# sangaboard_v02.net
KiCad netlist of a schematic drawn in EAGLE
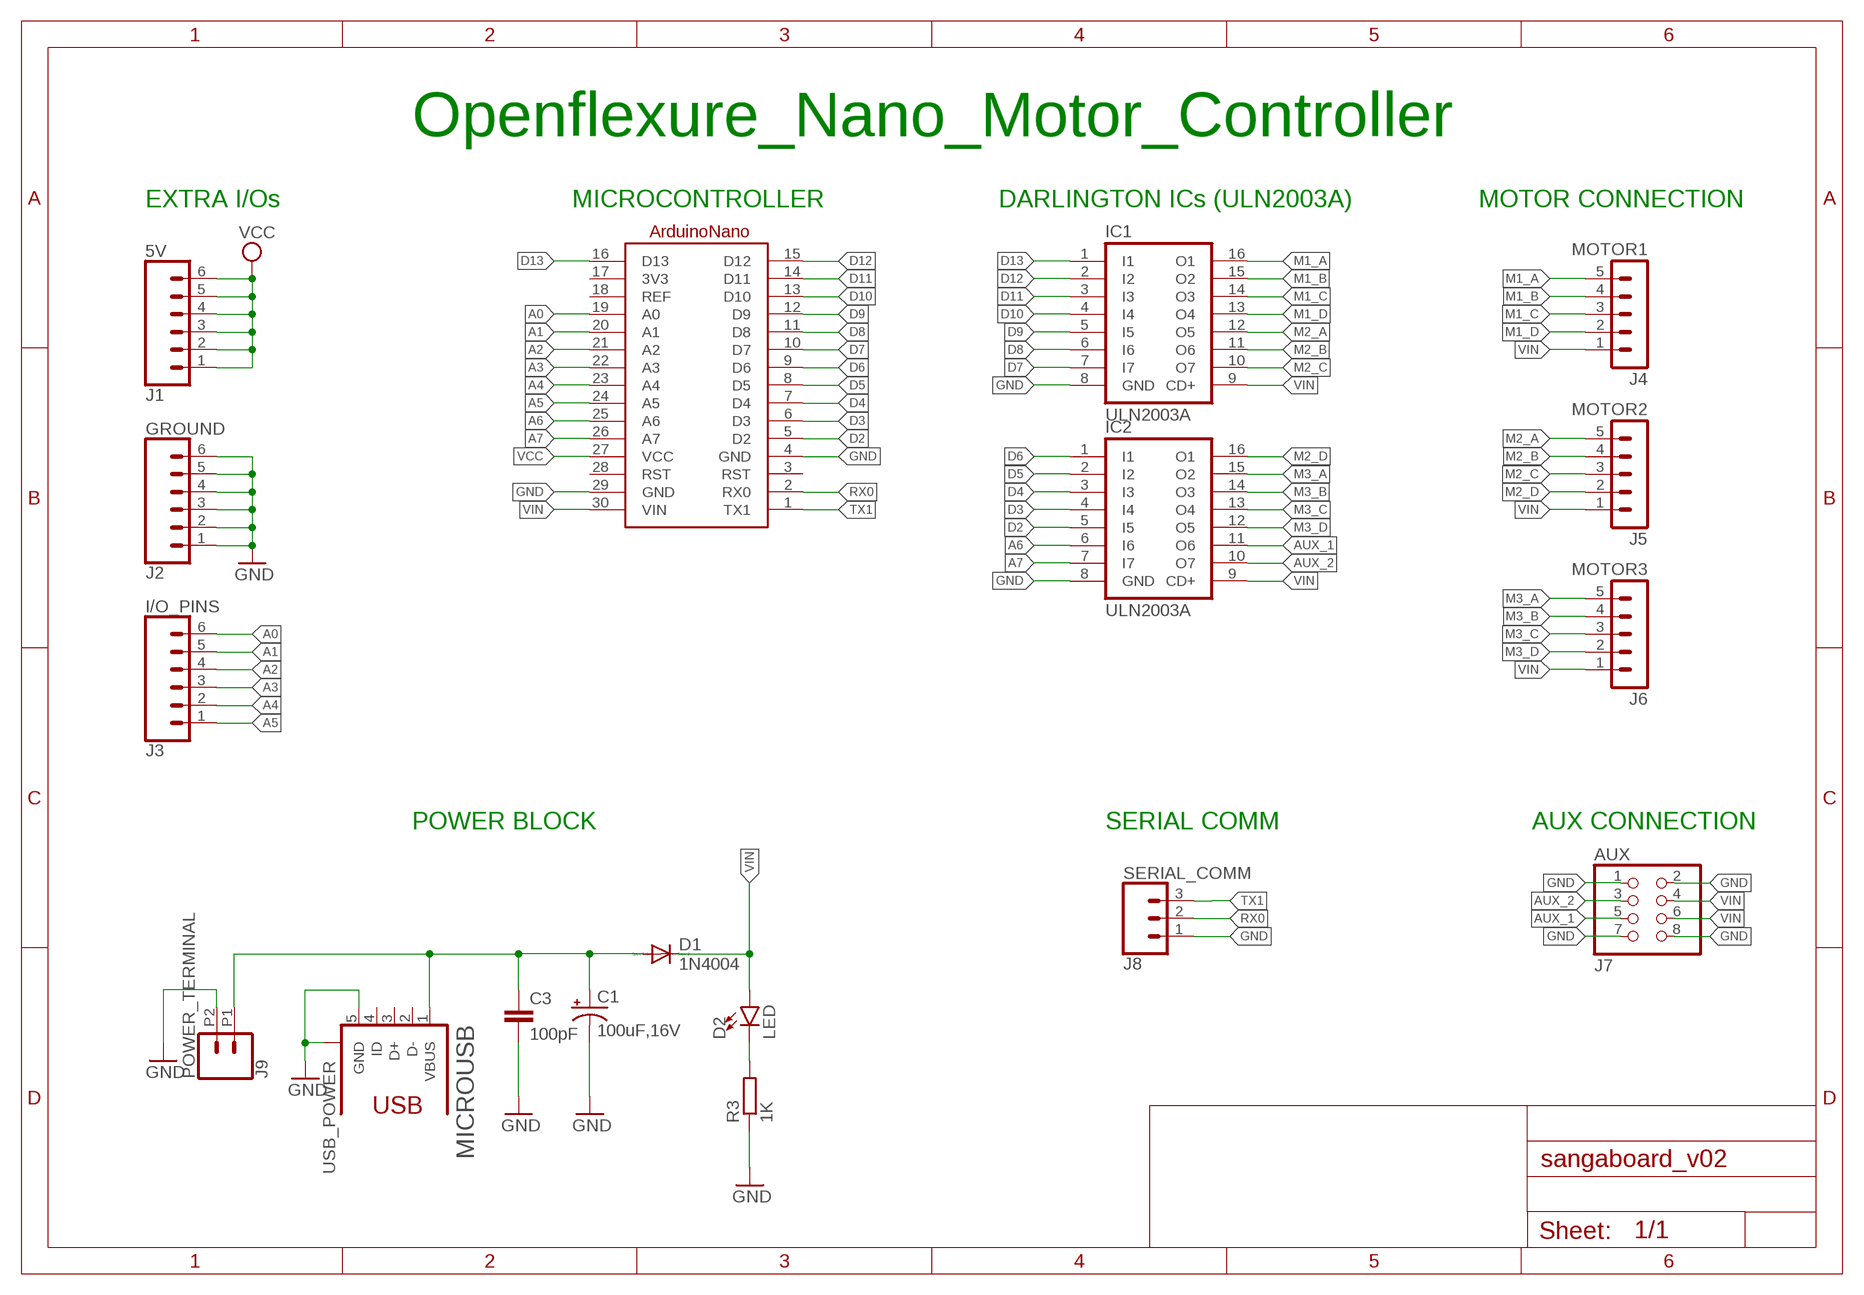
[diagram p0: schematic, sheet 1]

(export (version "E")
  (design (tool "Eeschema 10.0.6"))
  (components
    (comp (ref "5V")
      (value "J1")
      (footprint "eagle-import:1X06_NO_SILK")
      (libsource (lib "eagle-import") (part "CONN_06NO_SILK_NO_POP"))
    )
    (comp (ref "A1")
      (value "Arduino Nano")
      (footprint "eagle-import:ARDUINONANO")
      (libsource (lib "eagle-import") (part "ARDUINONANO"))
    )
    (comp (ref "AUX")
      (value "J7")
      (footprint "eagle-import:2X04")
      (libsource (lib "eagle-import") (part "PINHD-2X4"))
    )
    (comp (ref "C1")
      (value "100uF,16V")
      (footprint "eagle-import:CPOL-RADIAL-2.5MM-6.5MM")
      (libsource (lib "eagle-import") (part "100UF-POLAR-RADIAL-2.5MM-25V-20%"))
    )
    (comp (ref "C3")
      (value "100pF")
      (footprint "eagle-import:CAP-PTH-2.54")
      (libsource (lib "eagle-import") (part "22PF-PTH-2.54MM-200V-5%"))
    )
    (comp (ref "D1")
      (value "1N4004")
      (footprint "eagle-import:DO41-10")
      (libsource (lib "eagle-import") (part "1N4004"))
    )
    (comp (ref "D2")
      (value "LED")
      (footprint "eagle-import:LED_3MM")
      (libsource (lib "eagle-import") (part "LED3MM"))
    )
    (comp (ref "GROUND")
      (value "J2")
      (footprint "eagle-import:1X06_NO_SILK")
      (libsource (lib "eagle-import") (part "CONN_06NO_SILK_NO_POP"))
    )
    (comp (ref "I/O_PINS")
      (value "J3")
      (footprint "eagle-import:1X06_NO_SILK")
      (libsource (lib "eagle-import") (part "CONN_06NO_SILK_NO_POP"))
    )
    (comp (ref "IC1")
      (value "ULN2003A")
      (footprint "eagle-import:DIL16")
      (fields (field (name "MF") "STMicroelectronics"))
      (libsource (lib "eagle-import") (part "ULN2003AN"))
    )
    (comp (ref "IC2")
      (value "ULN2003A")
      (footprint "eagle-import:DIL16")
      (fields (field (name "MF") "STMicroelectronics"))
      (libsource (lib "eagle-import") (part "ULN2003AN"))
    )
    (comp (ref "MICROUSB")
      (value "USB_POWER")
      (footprint "eagle-import:1981584-1")
      (libsource (lib "eagle-import") (part "1981584-1"))
    )
    (comp (ref "MOTOR1")
      (value "J4")
      (footprint "eagle-import:MA05-1")
      (libsource (lib "eagle-import") (part "MA05-1"))
    )
    (comp (ref "MOTOR2")
      (value "J5")
      (footprint "eagle-import:MA05-1")
      (libsource (lib "eagle-import") (part "MA05-1"))
    )
    (comp (ref "MOTOR3")
      (value "J6")
      (footprint "eagle-import:MA05-1")
      (libsource (lib "eagle-import") (part "MA05-1"))
    )
    (comp (ref "POWER_TERMINAL")
      (value "J9")
      (footprint "eagle-import:1X02_2.54_SCREWTERM")
      (libsource (lib "eagle-import") (part "CONN_022.54MM_SCREWTERM"))
    )
    (comp (ref "R3")
      (value "1K")
      (footprint "eagle-import:0207_10")
      (libsource (lib "eagle-import") (part "R-EU_0207/10"))
    )
    (comp (ref "SERIAL_COMM")
      (value "J8")
      (footprint "eagle-import:1X03")
      (libsource (lib "eagle-import") (part "CONN_03"))
    )
  )
  (nets
    (net (code "1") (name "/3V3") (class "Default")
      (node (ref "A1") (pin "17") (pinfunction "3V3_17") (pintype "power_in"))
    )
    (net (code "2") (name "/REF") (class "Default")
      (node (ref "A1") (pin "18") (pinfunction "REF_18") (pintype "power_in"))
    )
    (net (code "3") (name "A0") (class "Default")
      (node (ref "A1") (pin "19") (pinfunction "A0_19") (pintype "input"))
      (node (ref "I/O_PINS") (pin "6") (pinfunction "6_6") (pintype "passive"))
    )
    (net (code "4") (name "A1") (class "Default")
      (node (ref "A1") (pin "20") (pinfunction "A1_20") (pintype "input"))
      (node (ref "I/O_PINS") (pin "5") (pinfunction "5_5") (pintype "passive"))
    )
    (net (code "5") (name "A2") (class "Default")
      (node (ref "A1") (pin "21") (pinfunction "A2_21") (pintype "input"))
      (node (ref "I/O_PINS") (pin "4") (pinfunction "4_4") (pintype "passive"))
    )
    (net (code "6") (name "A3") (class "Default")
      (node (ref "A1") (pin "22") (pinfunction "A3_22") (pintype "input"))
      (node (ref "I/O_PINS") (pin "3") (pinfunction "3_3") (pintype "passive"))
    )
    (net (code "7") (name "A4") (class "Default")
      (node (ref "A1") (pin "23") (pinfunction "A4_23") (pintype "input"))
      (node (ref "I/O_PINS") (pin "2") (pinfunction "2_2") (pintype "passive"))
    )
    (net (code "8") (name "A5") (class "Default")
      (node (ref "A1") (pin "24") (pinfunction "A5_24") (pintype "input"))
      (node (ref "I/O_PINS") (pin "1") (pinfunction "1_1") (pintype "passive"))
    )
    (net (code "9") (name "A6") (class "Default")
      (node (ref "A1") (pin "25") (pinfunction "A6_25") (pintype "input"))
      (node (ref "IC2") (pin "6") (pinfunction "I6_6") (pintype "input"))
    )
    (net (code "10") (name "A7") (class "Default")
      (node (ref "A1") (pin "26") (pinfunction "A7_26") (pintype "input"))
      (node (ref "IC2") (pin "7") (pinfunction "I7_7") (pintype "input"))
    )
    (net (code "11") (name "AUX_1") (class "Default")
      (node (ref "AUX") (pin "5") (pinfunction "5_5") (pintype "passive"))
      (node (ref "IC2") (pin "11") (pinfunction "O6_11") (pintype "open_collector"))
    )
    (net (code "12") (name "AUX_2") (class "Default")
      (node (ref "AUX") (pin "3") (pinfunction "3_3") (pintype "passive"))
      (node (ref "IC2") (pin "10") (pinfunction "O7_10") (pintype "open_collector"))
    )
    (net (code "13") (name "D2") (class "Default")
      (node (ref "A1") (pin "5") (pinfunction "D2_5") (pintype "output"))
      (node (ref "IC2") (pin "5") (pinfunction "I5_5") (pintype "input"))
    )
    (net (code "14") (name "D3") (class "Default")
      (node (ref "A1") (pin "6") (pinfunction "D3_6") (pintype "output"))
      (node (ref "IC2") (pin "4") (pinfunction "I4_4") (pintype "input"))
    )
    (net (code "15") (name "D4") (class "Default")
      (node (ref "A1") (pin "7") (pinfunction "D4_7") (pintype "output"))
      (node (ref "IC2") (pin "3") (pinfunction "I3_3") (pintype "input"))
    )
    (net (code "16") (name "D5") (class "Default")
      (node (ref "A1") (pin "8") (pinfunction "D5_8") (pintype "output"))
      (node (ref "IC2") (pin "2") (pinfunction "I2_2") (pintype "input"))
    )
    (net (code "17") (name "D6") (class "Default")
      (node (ref "A1") (pin "9") (pinfunction "D6_9") (pintype "output"))
      (node (ref "IC2") (pin "1") (pinfunction "I1_1") (pintype "input"))
    )
    (net (code "18") (name "D7") (class "Default")
      (node (ref "A1") (pin "10") (pinfunction "D7_10") (pintype "output"))
      (node (ref "IC1") (pin "7") (pinfunction "I7_7") (pintype "input"))
    )
    (net (code "19") (name "D8") (class "Default")
      (node (ref "A1") (pin "11") (pinfunction "D8_11") (pintype "output"))
      (node (ref "IC1") (pin "6") (pinfunction "I6_6") (pintype "input"))
    )
    (net (code "20") (name "D9") (class "Default")
      (node (ref "A1") (pin "12") (pinfunction "D9_12") (pintype "output"))
      (node (ref "IC1") (pin "5") (pinfunction "I5_5") (pintype "input"))
    )
    (net (code "21") (name "D10") (class "Default")
      (node (ref "A1") (pin "13") (pinfunction "D10_13") (pintype "output"))
      (node (ref "IC1") (pin "4") (pinfunction "I4_4") (pintype "input"))
    )
    (net (code "22") (name "D11") (class "Default")
      (node (ref "A1") (pin "14") (pinfunction "D11_14") (pintype "output"))
      (node (ref "IC1") (pin "3") (pinfunction "I3_3") (pintype "input"))
    )
    (net (code "23") (name "D12") (class "Default")
      (node (ref "A1") (pin "15") (pinfunction "D12_15") (pintype "output"))
      (node (ref "IC1") (pin "2") (pinfunction "I2_2") (pintype "input"))
    )
    (net (code "24") (name "D13") (class "Default")
      (node (ref "A1") (pin "16") (pinfunction "D13_16") (pintype "output"))
      (node (ref "IC1") (pin "1") (pinfunction "I1_1") (pintype "input"))
    )
    (net (code "25") (name "GND") (class "Default")
      (node (ref "A1") (pin "29") (pinfunction "GND_29") (pintype "power_in"))
      (node (ref "A1") (pin "4") (pinfunction "GND_4") (pintype "power_in"))
      (node (ref "AUX") (pin "1") (pinfunction "1_1") (pintype "passive"))
      (node (ref "AUX") (pin "2") (pinfunction "2_2") (pintype "passive"))
      (node (ref "AUX") (pin "7") (pinfunction "7_7") (pintype "passive"))
      (node (ref "AUX") (pin "8") (pinfunction "8_8") (pintype "passive"))
      (node (ref "C1") (pin "2") (pinfunction "-_2") (pintype "passive"))
      (node (ref "C3") (pin "2") (pinfunction "2_2") (pintype "passive"))
      (node (ref "GROUND") (pin "1") (pinfunction "1_1") (pintype "passive"))
      (node (ref "GROUND") (pin "2") (pinfunction "2_2") (pintype "passive"))
      (node (ref "GROUND") (pin "3") (pinfunction "3_3") (pintype "passive"))
      (node (ref "GROUND") (pin "4") (pinfunction "4_4") (pintype "passive"))
      (node (ref "GROUND") (pin "5") (pinfunction "5_5") (pintype "passive"))
      (node (ref "GROUND") (pin "6") (pinfunction "6_6") (pintype "passive"))
      (node (ref "IC1") (pin "8") (pinfunction "GND_8") (pintype "power_in"))
      (node (ref "IC2") (pin "8") (pinfunction "GND_8") (pintype "power_in"))
      (node (ref "MICROUSB") (pin "5") (pinfunction "GND_5") (pintype "passive"))
      (node (ref "MICROUSB") (pin "S1") (pinfunction "S1_S1") (pintype "passive"))
      (node (ref "POWER_TERMINAL") (pin "P2") (pinfunction "2_P2") (pintype "passive"))
      (node (ref "R3") (pin "1") (pinfunction "1_1") (pintype "passive"))
      (node (ref "SERIAL_COMM") (pin "1") (pinfunction "1_1") (pintype "passive"))
    )
    (net (code "26") (name "M1_A") (class "Default")
      (node (ref "IC1") (pin "16") (pinfunction "O1_16") (pintype "open_collector"))
      (node (ref "MOTOR1") (pin "5") (pinfunction "5_5") (pintype "passive"))
    )
    (net (code "27") (name "M1_B") (class "Default")
      (node (ref "IC1") (pin "15") (pinfunction "O2_15") (pintype "open_collector"))
      (node (ref "MOTOR1") (pin "4") (pinfunction "4_4") (pintype "passive"))
    )
    (net (code "28") (name "M1_C") (class "Default")
      (node (ref "IC1") (pin "14") (pinfunction "O3_14") (pintype "open_collector"))
      (node (ref "MOTOR1") (pin "3") (pinfunction "3_3") (pintype "passive"))
    )
    (net (code "29") (name "M1_D") (class "Default")
      (node (ref "IC1") (pin "13") (pinfunction "O4_13") (pintype "open_collector"))
      (node (ref "MOTOR1") (pin "2") (pinfunction "2_2") (pintype "passive"))
    )
    (net (code "30") (name "M2_A") (class "Default")
      (node (ref "IC1") (pin "12") (pinfunction "O5_12") (pintype "open_collector"))
      (node (ref "MOTOR2") (pin "5") (pinfunction "5_5") (pintype "passive"))
    )
    (net (code "31") (name "M2_B") (class "Default")
      (node (ref "IC1") (pin "11") (pinfunction "O6_11") (pintype "open_collector"))
      (node (ref "MOTOR2") (pin "4") (pinfunction "4_4") (pintype "passive"))
    )
    (net (code "32") (name "M2_C") (class "Default")
      (node (ref "IC1") (pin "10") (pinfunction "O7_10") (pintype "open_collector"))
      (node (ref "MOTOR2") (pin "3") (pinfunction "3_3") (pintype "passive"))
    )
    (net (code "33") (name "M2_D") (class "Default")
      (node (ref "IC2") (pin "16") (pinfunction "O1_16") (pintype "open_collector"))
      (node (ref "MOTOR2") (pin "2") (pinfunction "2_2") (pintype "passive"))
    )
    (net (code "34") (name "M3_A") (class "Default")
      (node (ref "IC2") (pin "15") (pinfunction "O2_15") (pintype "open_collector"))
      (node (ref "MOTOR3") (pin "5") (pinfunction "5_5") (pintype "passive"))
    )
    (net (code "35") (name "M3_B") (class "Default")
      (node (ref "IC2") (pin "14") (pinfunction "O3_14") (pintype "open_collector"))
      (node (ref "MOTOR3") (pin "4") (pinfunction "4_4") (pintype "passive"))
    )
    (net (code "36") (name "M3_C") (class "Default")
      (node (ref "IC2") (pin "13") (pinfunction "O4_13") (pintype "open_collector"))
      (node (ref "MOTOR3") (pin "3") (pinfunction "3_3") (pintype "passive"))
    )
    (net (code "37") (name "M3_D") (class "Default")
      (node (ref "IC2") (pin "12") (pinfunction "O5_12") (pintype "open_collector"))
      (node (ref "MOTOR3") (pin "2") (pinfunction "2_2") (pintype "passive"))
    )
    (net (code "38") (name "Net-(C1-+)") (class "Default")
      (node (ref "C1") (pin "1") (pinfunction "+_1") (pintype "passive"))
      (node (ref "C3") (pin "1") (pinfunction "1_1") (pintype "passive"))
      (node (ref "D1") (pin "A") (pinfunction "A_A") (pintype "passive"))
      (node (ref "MICROUSB") (pin "1") (pinfunction "VBUS_1") (pintype "passive"))
      (node (ref "POWER_TERMINAL") (pin "P1") (pinfunction "1_P1") (pintype "passive"))
    )
    (net (code "39") (name "Net-(D2-C)") (class "Default")
      (node (ref "D2") (pin "K") (pinfunction "C_K") (pintype "passive"))
      (node (ref "R3") (pin "2") (pinfunction "2_2") (pintype "passive"))
    )
    (net (code "40") (name "RX0") (class "Default")
      (node (ref "A1") (pin "2") (pinfunction "RX0_2") (pintype "bidirectional"))
      (node (ref "SERIAL_COMM") (pin "2") (pinfunction "2_2") (pintype "passive"))
    )
    (net (code "41") (name "TX1") (class "Default")
      (node (ref "A1") (pin "1") (pinfunction "TX1_1") (pintype "bidirectional"))
      (node (ref "SERIAL_COMM") (pin "3") (pinfunction "3_3") (pintype "passive"))
    )
    (net (code "42") (name "VCC") (class "Default")
      (node (ref "5V") (pin "1") (pinfunction "1_1") (pintype "passive"))
      (node (ref "5V") (pin "2") (pinfunction "2_2") (pintype "passive"))
      (node (ref "5V") (pin "3") (pinfunction "3_3") (pintype "passive"))
      (node (ref "5V") (pin "4") (pinfunction "4_4") (pintype "passive"))
      (node (ref "5V") (pin "5") (pinfunction "5_5") (pintype "passive"))
      (node (ref "5V") (pin "6") (pinfunction "6_6") (pintype "passive"))
      (node (ref "A1") (pin "27") (pinfunction "VCC_27") (pintype "power_in"))
    )
    (net (code "43") (name "VIN") (class "Default")
      (node (ref "A1") (pin "30") (pinfunction "VIN_30") (pintype "power_in"))
      (node (ref "AUX") (pin "4") (pinfunction "4_4") (pintype "passive"))
      (node (ref "AUX") (pin "6") (pinfunction "6_6") (pintype "passive"))
      (node (ref "D1") (pin "C") (pinfunction "C_C") (pintype "passive"))
      (node (ref "D2") (pin "A") (pinfunction "A_A") (pintype "passive"))
      (node (ref "IC1") (pin "9") (pinfunction "CD+_9") (pintype "passive"))
      (node (ref "IC2") (pin "9") (pinfunction "CD+_9") (pintype "passive"))
      (node (ref "MOTOR1") (pin "1") (pinfunction "1_1") (pintype "passive"))
      (node (ref "MOTOR2") (pin "1") (pinfunction "1_1") (pintype "passive"))
      (node (ref "MOTOR3") (pin "1") (pinfunction "1_1") (pintype "passive"))
    )
    (net (code "44") (name "unconnected-(A1-RST-Pad3)") (class "Default")
      (node (ref "A1") (pin "3") (pinfunction "RST_3") (pintype "input"))
    )
    (net (code "45") (name "unconnected-(A1-RST-Pad28)") (class "Default")
      (node (ref "A1") (pin "28") (pinfunction "RST_28") (pintype "input"))
    )
    (net (code "46") (name "unconnected-(MICROUSB-D+-Pad3)") (class "Default")
      (node (ref "MICROUSB") (pin "3") (pinfunction "D+_3") (pintype "passive"))
    )
    (net (code "47") (name "unconnected-(MICROUSB-D--Pad2)") (class "Default")
      (node (ref "MICROUSB") (pin "2") (pinfunction "D-_2") (pintype "passive"))
    )
    (net (code "48") (name "unconnected-(MICROUSB-ID-Pad4)") (class "Default")
      (node (ref "MICROUSB") (pin "4") (pinfunction "ID_4") (pintype "passive"))
    )
  )
)
